# 1-Schematic_LiveTelemtry.net
KiCad netlist of a schematic drawn in EasyEDA
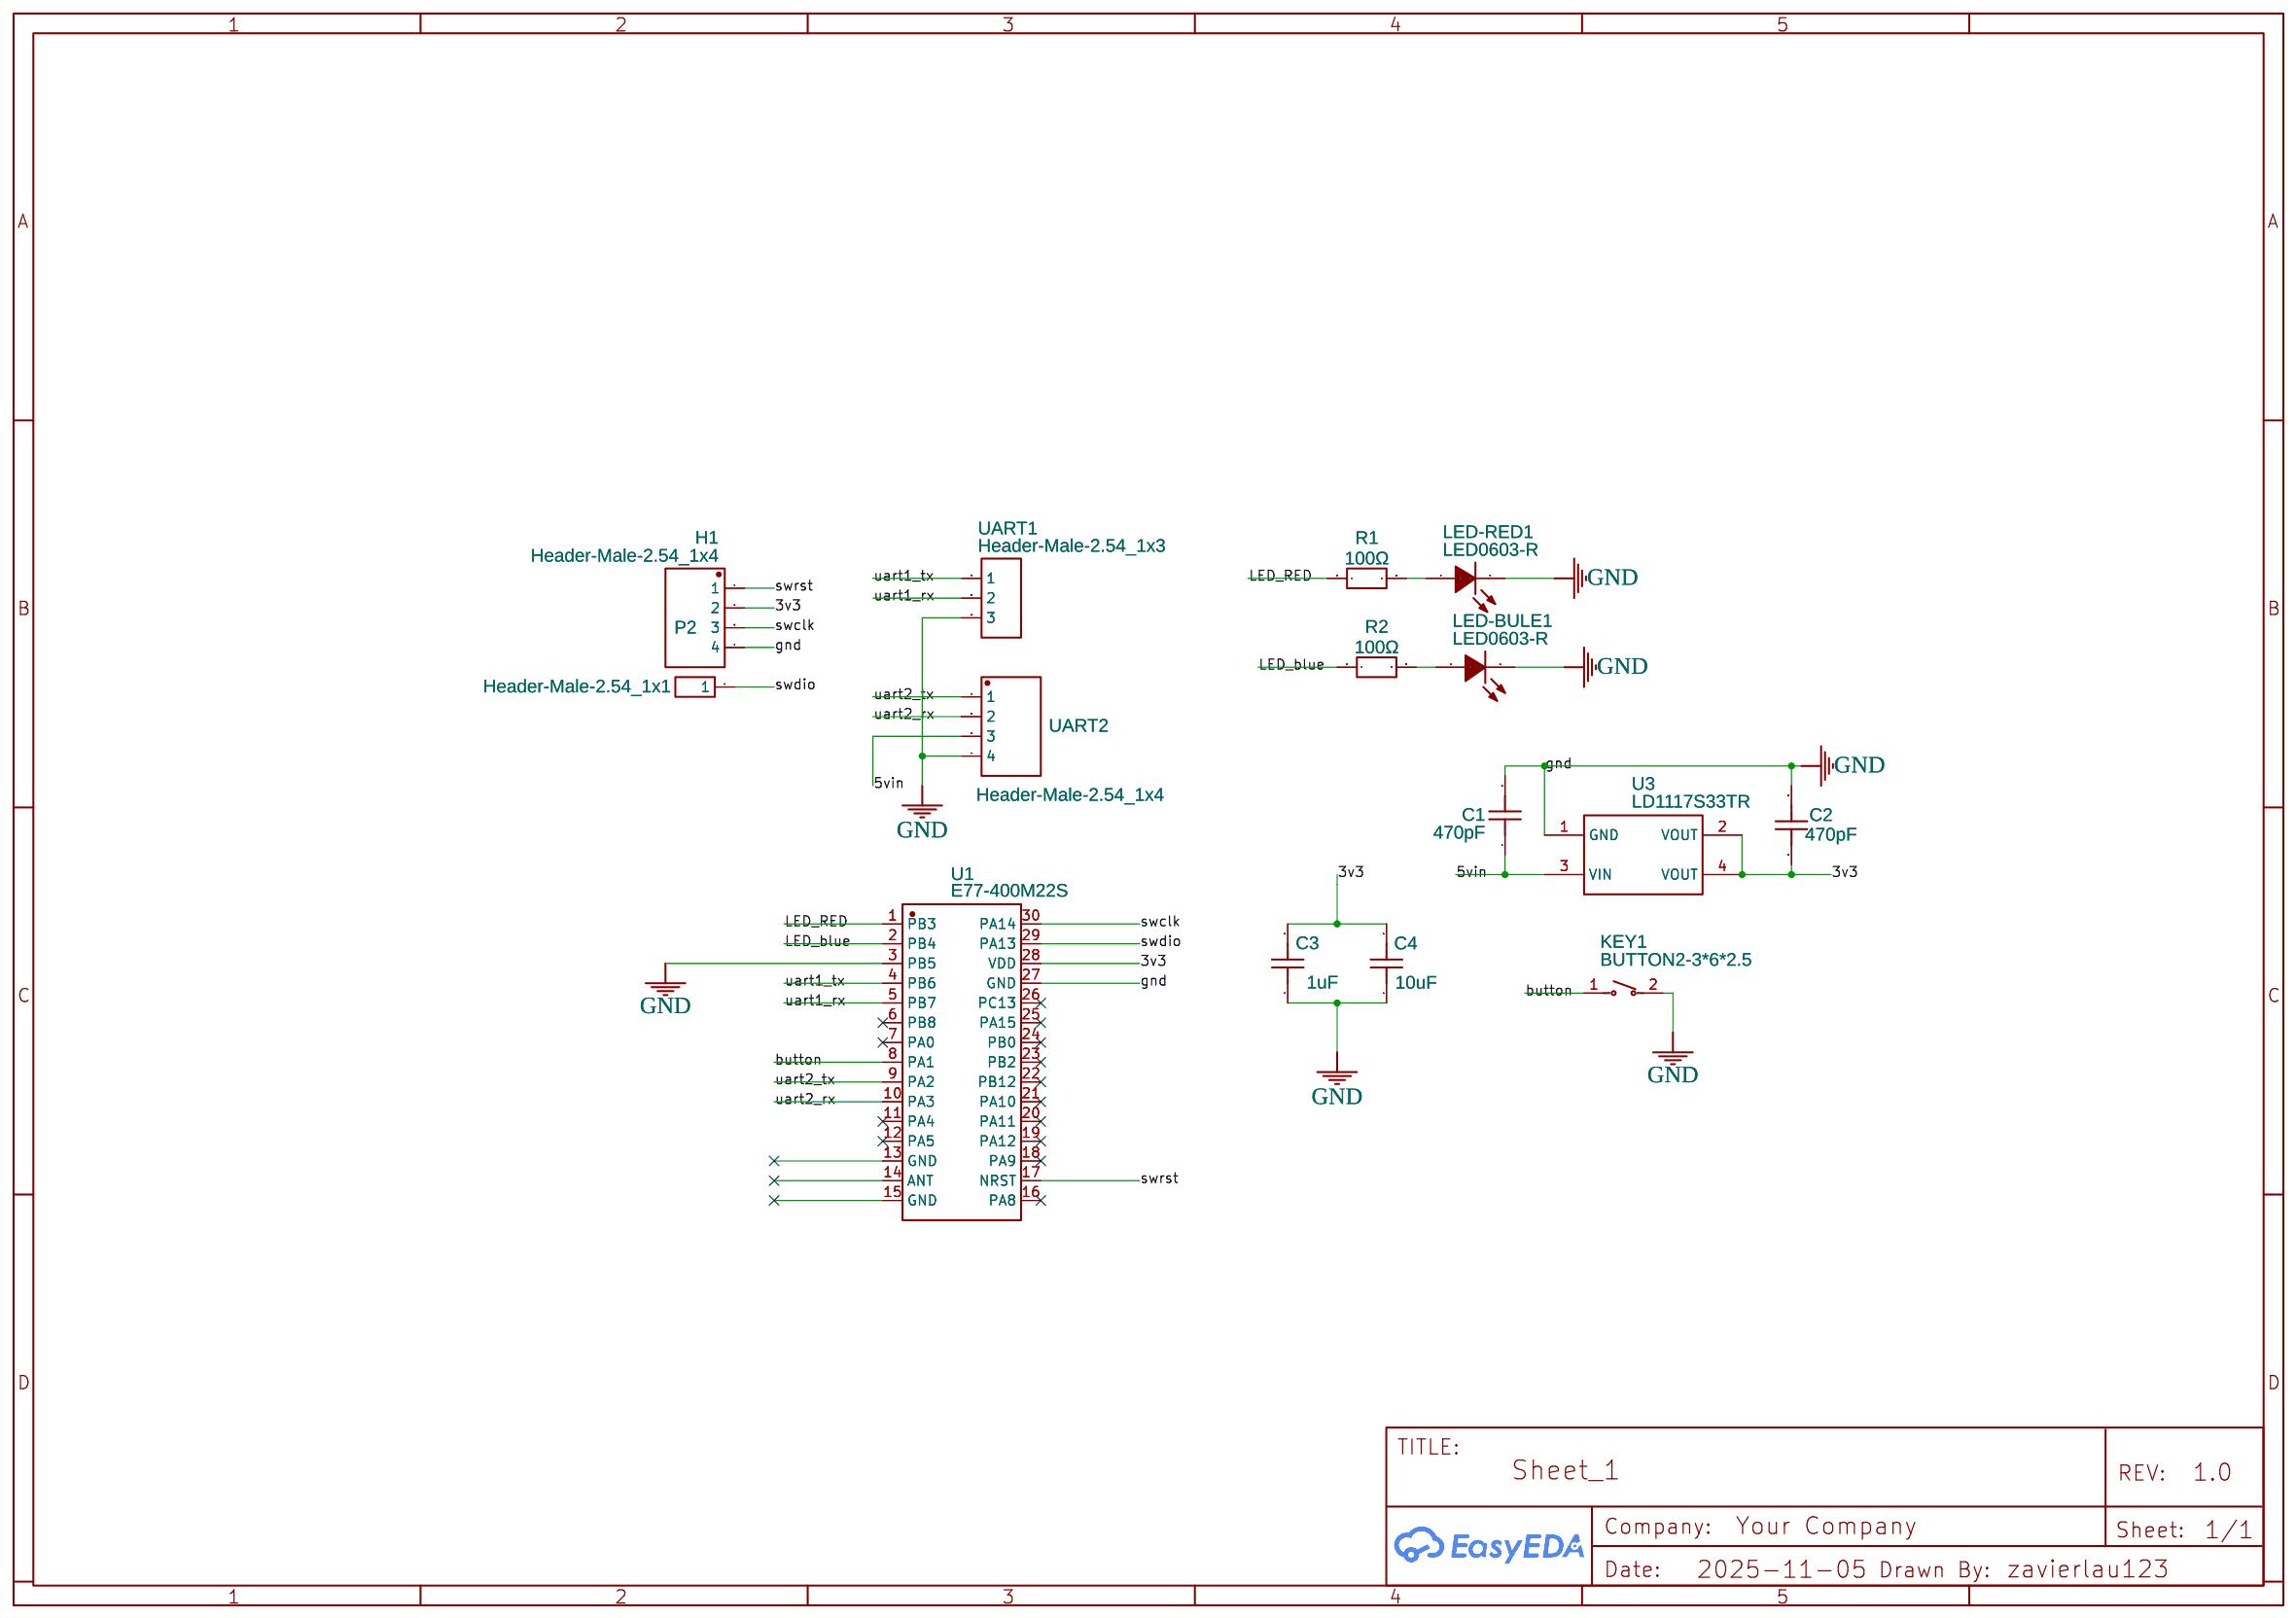
[diagram p0: schematic sheet]

(export (version "E")
  (design (tool "Eeschema 10.0.6"))
  (components
    (comp (ref "C1")
      (value "470pF")
      (fields (field (name "Manufacturer Part") "C1608CH2A471J080AA") (field (name "Manufacturer") "TDK"))
      (libsource (lib "") (part "C1608CH2A471J080AA"))
    )
    (comp (ref "C2")
      (value "470pF")
      (fields (field (name "Manufacturer Part") "C1608CH2A471J080AA") (field (name "Manufacturer") "TDK"))
      (libsource (lib "") (part "C1608CH2A471J080AA"))
    )
    (comp (ref "C3")
      (value "1uF")
      (fields (field (name "Manufacturer Part") "C1608CH2A471J080AA") (field (name "Manufacturer") "TDK"))
      (libsource (lib "") (part "C1608CH2A471J080AA"))
    )
    (comp (ref "C4")
      (value "10uF")
      (fields (field (name "Manufacturer Part") "C1608CH2A471J080AA") (field (name "Manufacturer") "TDK"))
      (libsource (lib "") (part "C1608CH2A471J080AA"))
    )
    (comp (ref "H1")
      (value "Header-Male-2.54_1x4")
      (fields (field (name "Manufacturer Part") "B-2100S04P-A110") (field (name "Manufacturer") "Ckmtw(灿科盟)"))
      (libsource (lib "") (part "Header-Male-2.54_1x4_1"))
    )
    (comp (ref "KEY1") (value "BUTTON2-3*6*2.5") (libsource (lib "") (part "BUTTON2-3*6*2.5")))
    (comp (ref "LED-BULE1") (value "LED0603-R") (libsource (lib "") (part "LED0603-R")))
    (comp (ref "LED-RED1") (value "LED0603-R") (libsource (lib "") (part "LED0603-R_1")))
    (comp (ref "P2")
      (value "Header-Male-2.54_1x1")
      (fields (field (name "Manufacturer Part") "2.54-1*1P针") (field (name "Manufacturer") "BOOMELE(博穆精密)"))
      (libsource (lib "") (part "Header-Male-2.54_1x1"))
    )
    (comp (ref "R1")
      (value "100Ω")
      (fields
        (field (name "Manufacturer Part") "HoAR0603-1/10W-100R-0.1%-TCR25")
        (field (name "Manufacturer") "Milliohm(毫欧)")
      )
      (libsource (lib "") (part "HOAR0603-1/10W-100R-0.1%-TCR25"))
    )
    (comp (ref "R2")
      (value "100Ω")
      (fields
        (field (name "Manufacturer Part") "HoAR0603-1/10W-100R-0.1%-TCR25")
        (field (name "Manufacturer") "Milliohm(毫欧)")
      )
      (libsource (lib "") (part "HOAR0603-1/10W-100R-0.1%-TCR25"))
    )
    (comp (ref "U1")
      (value "E77-400M22S")
      (fields (field (name "Manufacturer") "EBYTE(亿佰特)"))
      (libsource (lib "") (part "E77-400M22S"))
    )
    (comp (ref "U3")
      (value "LD1117S33TR")
      (fields (field (name "Manufacturer") "ST(意法半导体)"))
      (libsource (lib "") (part "LD1117S33TR"))
    )
    (comp (ref "UART1")
      (value "Header-Male-2.54_1x3")
      (fields (field (name "Manufacturer Part") "2.54-1*3P针") (field (name "Manufacturer") "BOOMELE(博穆精密)"))
      (libsource (lib "") (part "Header-Male-2.54_1x3"))
    )
    (comp (ref "UART2")
      (value "Header-Male-2.54_1x4")
      (fields (field (name "Manufacturer Part") "B-2100S04P-A110") (field (name "Manufacturer") "Ckmtw(灿科盟)"))
      (libsource (lib "") (part "Header-Male-2.54_1x4"))
    )
  )
  (nets
    (net (code "1") (name "/3v3") (class "Default")
      (node (ref "C2") (pin "1") (pinfunction "1_1") (pintype "unspecified"))
      (node (ref "C3") (pin "2") (pinfunction "2_2") (pintype "unspecified"))
      (node (ref "C4") (pin "2") (pinfunction "2_2") (pintype "unspecified"))
      (node (ref "H1") (pin "2") (pinfunction "2_2") (pintype "unspecified"))
      (node (ref "U1") (pin "28") (pinfunction "VDD_28") (pintype "unspecified"))
      (node (ref "U3") (pin "2") (pinfunction "VOUT_2") (pintype "unspecified"))
      (node (ref "U3") (pin "4") (pinfunction "VOUT_4") (pintype "unspecified"))
    )
    (net (code "2") (name "/5vin") (class "Default")
      (node (ref "C1") (pin "1") (pinfunction "1_1") (pintype "unspecified"))
      (node (ref "U3") (pin "3") (pinfunction "VIN_3") (pintype "unspecified"))
      (node (ref "UART2") (pin "3") (pinfunction "3_3") (pintype "unspecified"))
    )
    (net (code "3") (name "/LED_RED") (class "Default")
      (node (ref "R1") (pin "1") (pinfunction "1_1") (pintype "unspecified"))
      (node (ref "U1") (pin "1") (pinfunction "PB3_1") (pintype "unspecified"))
    )
    (net (code "4") (name "/LED_blue") (class "Default")
      (node (ref "R2") (pin "1") (pinfunction "1_1") (pintype "unspecified"))
      (node (ref "U1") (pin "2") (pinfunction "PB4_2") (pintype "unspecified"))
    )
    (net (code "5") (name "/button") (class "Default")
      (node (ref "KEY1") (pin "1") (pinfunction "1_1") (pintype "unspecified"))
      (node (ref "U1") (pin "8") (pinfunction "PA1_8") (pintype "unspecified"))
    )
    (net (code "6") (name "/swclk") (class "Default")
      (node (ref "H1") (pin "3") (pinfunction "3_3") (pintype "unspecified"))
      (node (ref "U1") (pin "30") (pinfunction "PA14_30") (pintype "unspecified"))
    )
    (net (code "7") (name "/swdio") (class "Default")
      (node (ref "P2") (pin "1") (pinfunction "1_1") (pintype "input"))
      (node (ref "U1") (pin "29") (pinfunction "PA13_29") (pintype "unspecified"))
    )
    (net (code "8") (name "/swrst") (class "Default")
      (node (ref "H1") (pin "1") (pinfunction "1_1") (pintype "unspecified"))
      (node (ref "U1") (pin "17") (pinfunction "NRST_17") (pintype "unspecified"))
    )
    (net (code "9") (name "/uart1_rx") (class "Default")
      (node (ref "U1") (pin "5") (pinfunction "PB7_5") (pintype "unspecified"))
      (node (ref "UART1") (pin "2") (pinfunction "2_2") (pintype "input"))
    )
    (net (code "10") (name "/uart1_tx") (class "Default")
      (node (ref "U1") (pin "4") (pinfunction "PB6_4") (pintype "unspecified"))
      (node (ref "UART1") (pin "1") (pinfunction "1_1") (pintype "input"))
    )
    (net (code "11") (name "/uart2_rx") (class "Default")
      (node (ref "U1") (pin "10") (pinfunction "PA3_10") (pintype "unspecified"))
      (node (ref "UART2") (pin "2") (pinfunction "2_2") (pintype "unspecified"))
    )
    (net (code "12") (name "/uart2_tx") (class "Default")
      (node (ref "U1") (pin "9") (pinfunction "PA2_9") (pintype "unspecified"))
      (node (ref "UART2") (pin "1") (pinfunction "1_1") (pintype "unspecified"))
    )
    (net (code "13") (name "GND") (class "Default")
      (node (ref "C1") (pin "2") (pinfunction "2_2") (pintype "unspecified"))
      (node (ref "C2") (pin "2") (pinfunction "2_2") (pintype "unspecified"))
      (node (ref "C3") (pin "1") (pinfunction "1_1") (pintype "unspecified"))
      (node (ref "C4") (pin "1") (pinfunction "1_1") (pintype "unspecified"))
      (node (ref "H1") (pin "4") (pinfunction "4_4") (pintype "unspecified"))
      (node (ref "KEY1") (pin "2") (pinfunction "2_2") (pintype "unspecified"))
      (node (ref "LED-BULE1") (pin "2") (pinfunction "K_2") (pintype "unspecified"))
      (node (ref "LED-RED1") (pin "2") (pinfunction "K_2") (pintype "unspecified"))
      (node (ref "U1") (pin "27") (pinfunction "GND_27") (pintype "unspecified"))
      (node (ref "U1") (pin "3") (pinfunction "PB5_3") (pintype "unspecified"))
      (node (ref "U3") (pin "1") (pinfunction "GND_1") (pintype "unspecified"))
      (node (ref "UART1") (pin "3") (pinfunction "3_3") (pintype "input"))
      (node (ref "UART2") (pin "4") (pinfunction "4_4") (pintype "unspecified"))
    )
    (net (code "14") (name "Net-(LED-BULE1-A)") (class "Default")
      (node (ref "LED-BULE1") (pin "1") (pinfunction "A_1") (pintype "unspecified"))
      (node (ref "R2") (pin "2") (pinfunction "2_2") (pintype "unspecified"))
    )
    (net (code "15") (name "Net-(LED-RED1-A)") (class "Default")
      (node (ref "LED-RED1") (pin "1") (pinfunction "A_1") (pintype "unspecified"))
      (node (ref "R1") (pin "2") (pinfunction "2_2") (pintype "unspecified"))
    )
    (net (code "16") (name "unconnected-(U1-ANT-Pad14)") (class "Default")
      (node (ref "U1") (pin "14") (pinfunction "ANT_14") (pintype "unspecified+no_connect"))
    )
    (net (code "17") (name "unconnected-(U1-GND-Pad13)") (class "Default")
      (node (ref "U1") (pin "13") (pinfunction "GND_13") (pintype "unspecified+no_connect"))
    )
    (net (code "18") (name "unconnected-(U1-GND-Pad15)") (class "Default")
      (node (ref "U1") (pin "15") (pinfunction "GND_15") (pintype "unspecified+no_connect"))
    )
    (net (code "19") (name "unconnected-(U1-PA0-Pad7)") (class "Default")
      (node (ref "U1") (pin "7") (pinfunction "PA0_7") (pintype "unspecified+no_connect"))
    )
    (net (code "20") (name "unconnected-(U1-PA4-Pad11)") (class "Default")
      (node (ref "U1") (pin "11") (pinfunction "PA4_11") (pintype "unspecified+no_connect"))
    )
    (net (code "21") (name "unconnected-(U1-PA5-Pad12)") (class "Default")
      (node (ref "U1") (pin "12") (pinfunction "PA5_12") (pintype "unspecified+no_connect"))
    )
    (net (code "22") (name "unconnected-(U1-PA8-Pad16)") (class "Default")
      (node (ref "U1") (pin "16") (pinfunction "PA8_16") (pintype "unspecified+no_connect"))
    )
    (net (code "23") (name "unconnected-(U1-PA9-Pad18)") (class "Default")
      (node (ref "U1") (pin "18") (pinfunction "PA9_18") (pintype "unspecified+no_connect"))
    )
    (net (code "24") (name "unconnected-(U1-PA10-Pad21)") (class "Default")
      (node (ref "U1") (pin "21") (pinfunction "PA10_21") (pintype "unspecified+no_connect"))
    )
    (net (code "25") (name "unconnected-(U1-PA11-Pad20)") (class "Default")
      (node (ref "U1") (pin "20") (pinfunction "PA11_20") (pintype "unspecified+no_connect"))
    )
    (net (code "26") (name "unconnected-(U1-PA12-Pad19)") (class "Default")
      (node (ref "U1") (pin "19") (pinfunction "PA12_19") (pintype "unspecified+no_connect"))
    )
    (net (code "27") (name "unconnected-(U1-PA15-Pad25)") (class "Default")
      (node (ref "U1") (pin "25") (pinfunction "PA15_25") (pintype "unspecified+no_connect"))
    )
    (net (code "28") (name "unconnected-(U1-PB0-Pad24)") (class "Default")
      (node (ref "U1") (pin "24") (pinfunction "PB0_24") (pintype "unspecified+no_connect"))
    )
    (net (code "29") (name "unconnected-(U1-PB2-Pad23)") (class "Default")
      (node (ref "U1") (pin "23") (pinfunction "PB2_23") (pintype "unspecified+no_connect"))
    )
    (net (code "30") (name "unconnected-(U1-PB8-Pad6)") (class "Default")
      (node (ref "U1") (pin "6") (pinfunction "PB8_6") (pintype "unspecified+no_connect"))
    )
    (net (code "31") (name "unconnected-(U1-PB12-Pad22)") (class "Default")
      (node (ref "U1") (pin "22") (pinfunction "PB12_22") (pintype "unspecified+no_connect"))
    )
    (net (code "32") (name "unconnected-(U1-PC13-Pad26)") (class "Default")
      (node (ref "U1") (pin "26") (pinfunction "PC13_26") (pintype "unspecified+no_connect"))
    )
  )
)
